# schematic-easyeda.net
KiCad netlist of a schematic drawn in EasyEDA
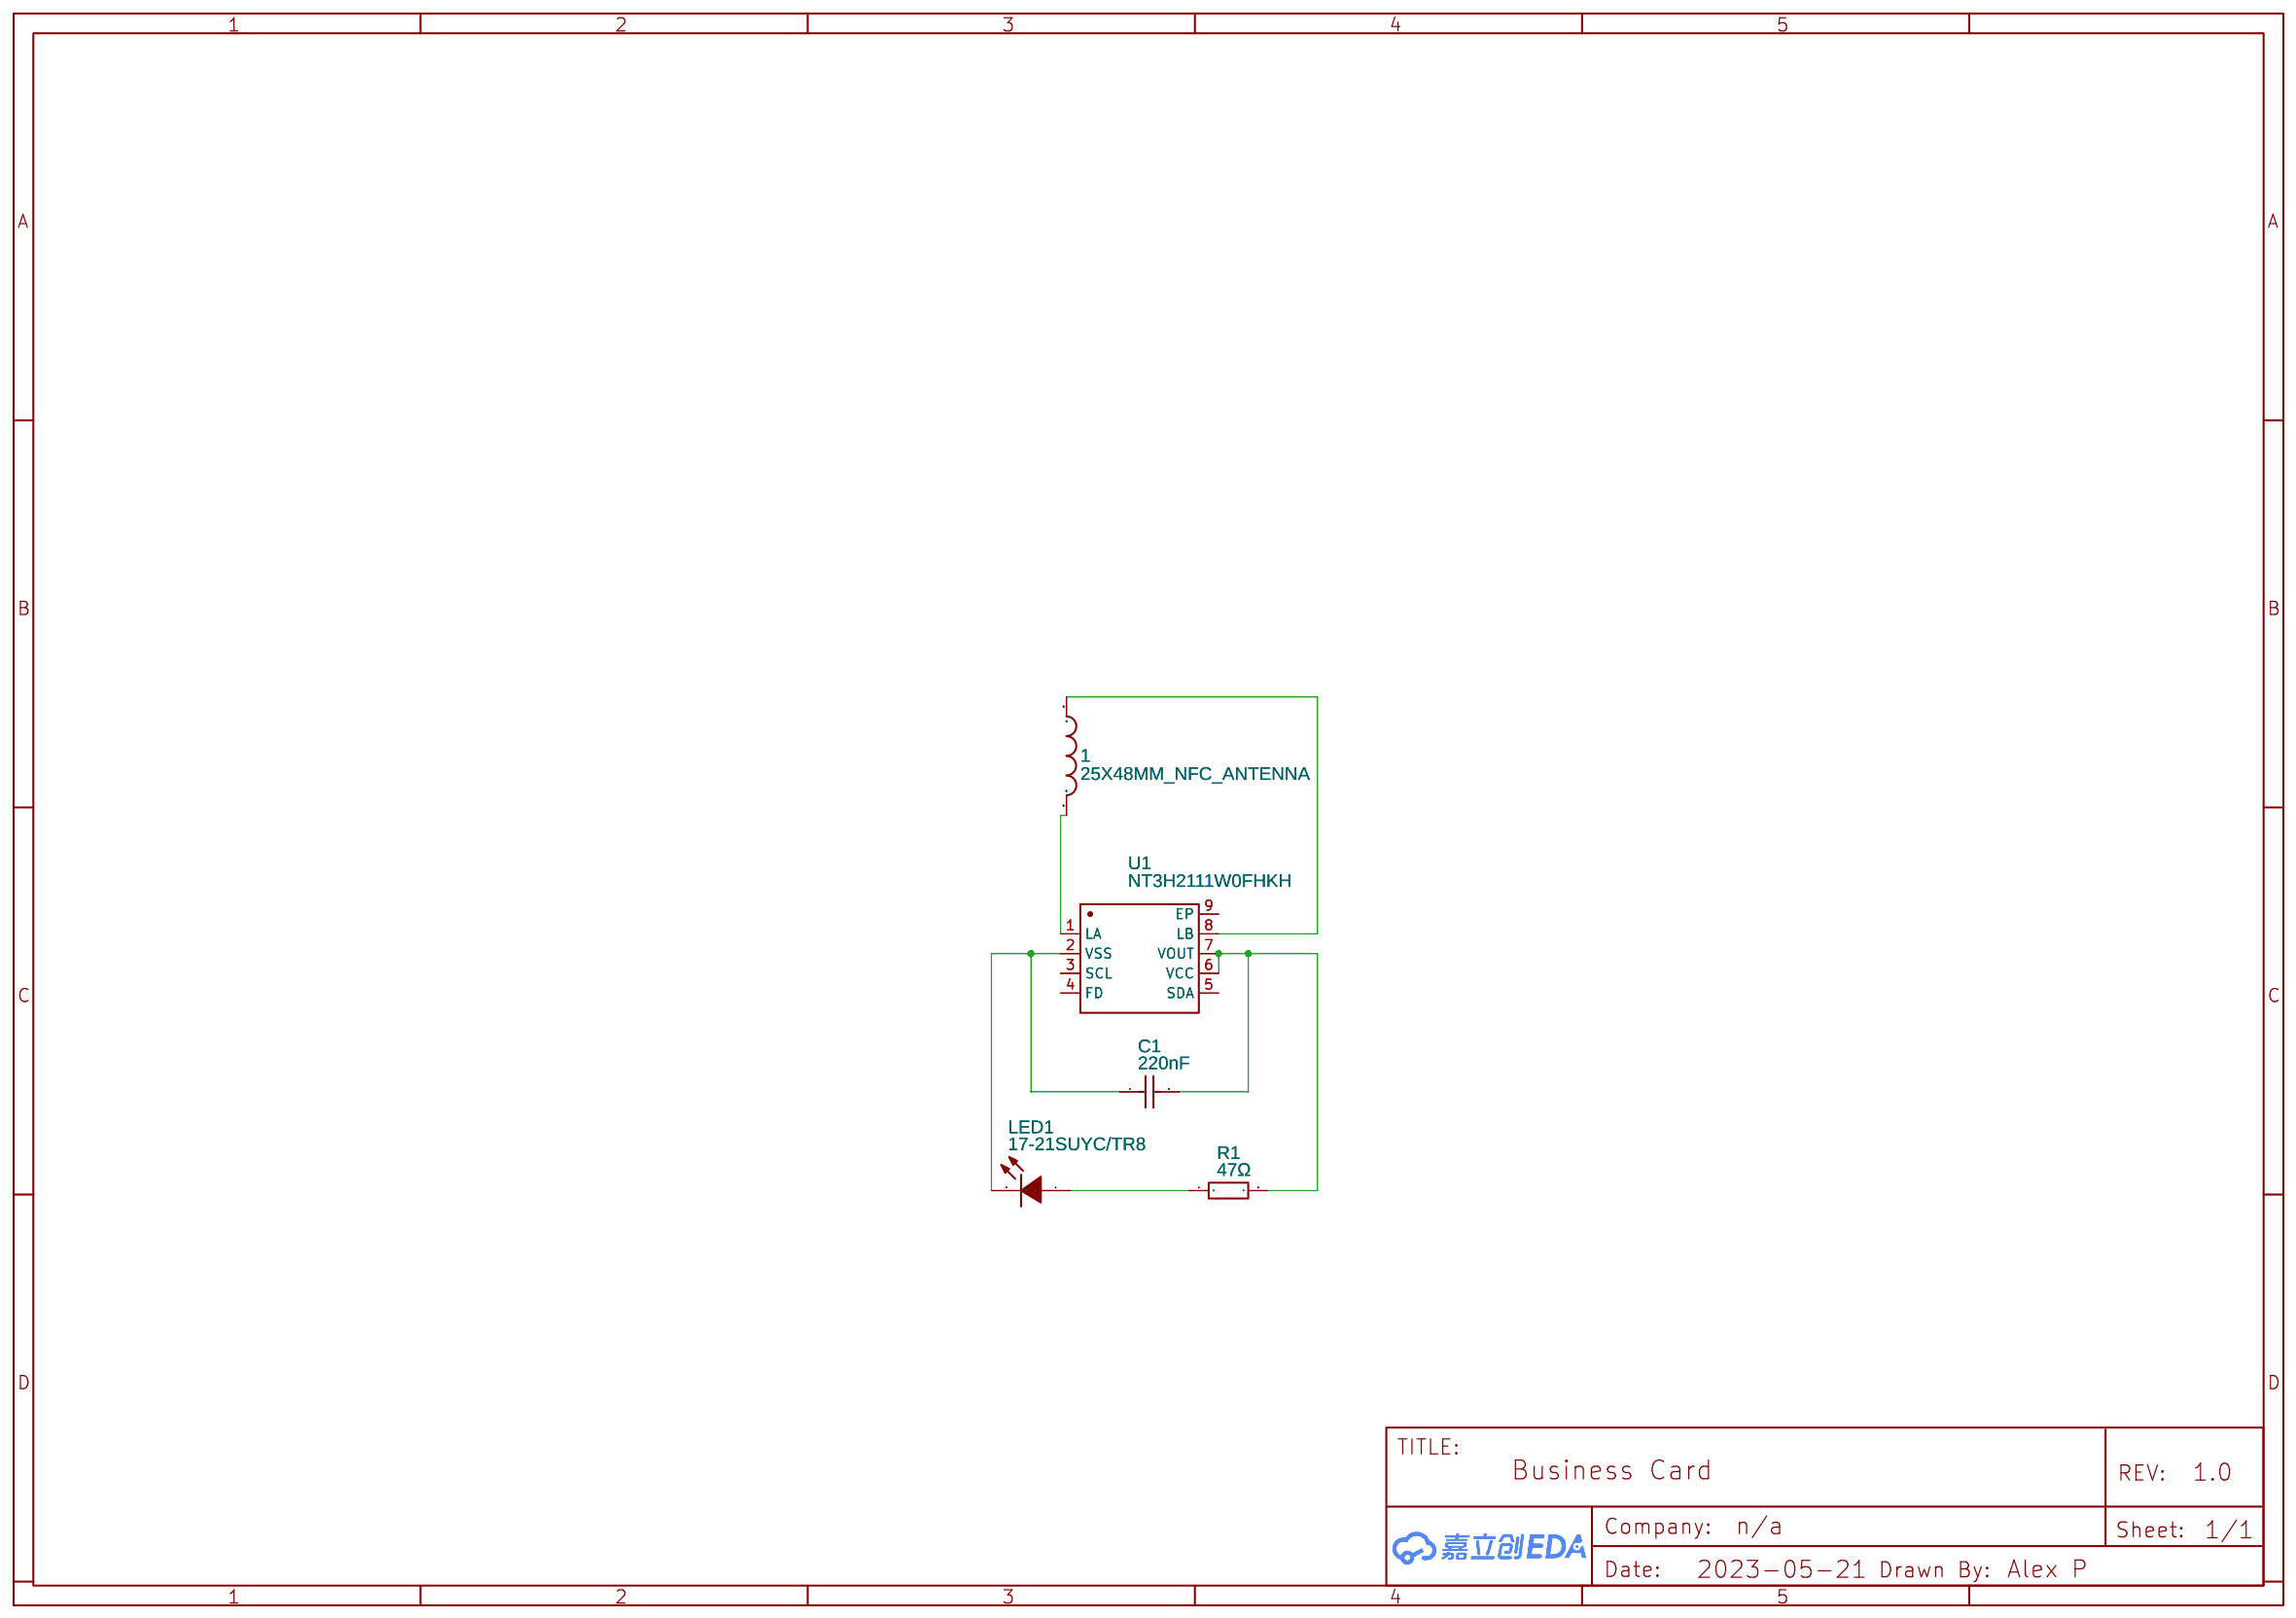
[diagram p0: schematic sheet]

(export (version "E")
  (design (tool "Eeschema 10.0.6"))
  (components
    (comp (ref "1") (value "25X48MM_NFC_ANTENNA") (libsource (lib "") (part "25X48MM_NFC_ANTENNA")))
    (comp (ref "C1")
      (value "220nF")
      (fields
        (field (name "Manufacturer Part") "CL10B224KA8NNNC")
        (field (name "Manufacturer") "SAMSUNG(三星)")
      )
      (libsource (lib "") (part "CL10B224KA8NNNC"))
    )
    (comp (ref "LED1")
      (value "17-21SUYC/TR8")
      (fields (field (name "Manufacturer Part") "KT-0805黄灯") (field (name "Manufacturer") "KENTO"))
      (libsource (lib "") (part "17-21SUYC/TR8"))
    )
    (comp (ref "R1")
      (value "47Ω")
      (fields
        (field (name "Manufacturer Part") "0603WAF470JT5E")
        (field (name "Manufacturer") "UNI-ROYAL(厚声)")
      )
      (libsource (lib "") (part "0603WAF470JT5E"))
    )
    (comp (ref "U1")
      (value "NT3H2111W0FHKH")
      (fields (field (name "Manufacturer") "NXP(恩智浦)"))
      (libsource (lib "") (part "NT3H2111W0FHKH"))
    )
  )
  (nets
    (net (code "1") (name "Net-(LED1-+)") (class "Default")
      (node (ref "LED1") (pin "1") (pinfunction "+_1") (pintype "unspecified"))
      (node (ref "R1") (pin "1") (pinfunction "1_1") (pintype "input"))
    )
    (net (code "2") (name "Net-(LED1--)") (class "Default")
      (node (ref "C1") (pin "1") (pinfunction "1_1") (pintype "input"))
      (node (ref "LED1") (pin "2") (pinfunction "-_2") (pintype "unspecified"))
      (node (ref "U1") (pin "2") (pinfunction "VSS_2") (pintype "unspecified"))
    )
    (net (code "3") (name "Net-(U1-LA)") (class "Default")
      (node (ref "1") (pin "P$2") (pinfunction "P$2_P$2") (pintype "bidirectional"))
      (node (ref "U1") (pin "1") (pinfunction "LA_1") (pintype "unspecified"))
    )
    (net (code "4") (name "Net-(U1-LB)") (class "Default")
      (node (ref "1") (pin "P$1") (pinfunction "P$1_P$1") (pintype "bidirectional"))
      (node (ref "U1") (pin "8") (pinfunction "LB_8") (pintype "unspecified"))
    )
    (net (code "5") (name "Net-(U1-VCC)") (class "Default")
      (node (ref "C1") (pin "2") (pinfunction "2_2") (pintype "input"))
      (node (ref "R1") (pin "2") (pinfunction "2_2") (pintype "input"))
      (node (ref "U1") (pin "6") (pinfunction "VCC_6") (pintype "unspecified"))
      (node (ref "U1") (pin "7") (pinfunction "VOUT_7") (pintype "unspecified"))
    )
    (net (code "6") (name "unconnected-(U1-EP-Pad9)") (class "Default")
      (node (ref "U1") (pin "9") (pinfunction "EP_9") (pintype "unspecified"))
    )
    (net (code "7") (name "unconnected-(U1-FD-Pad4)") (class "Default")
      (node (ref "U1") (pin "4") (pinfunction "FD_4") (pintype "unspecified"))
    )
    (net (code "8") (name "unconnected-(U1-SCL-Pad3)") (class "Default")
      (node (ref "U1") (pin "3") (pinfunction "SCL_3") (pintype "unspecified"))
    )
    (net (code "9") (name "unconnected-(U1-SDA-Pad5)") (class "Default")
      (node (ref "U1") (pin "5") (pinfunction "SDA_5") (pintype "unspecified"))
    )
  )
)
